# Microcontroller.net
KiCad netlist of a schematic drawn in Altium Designer
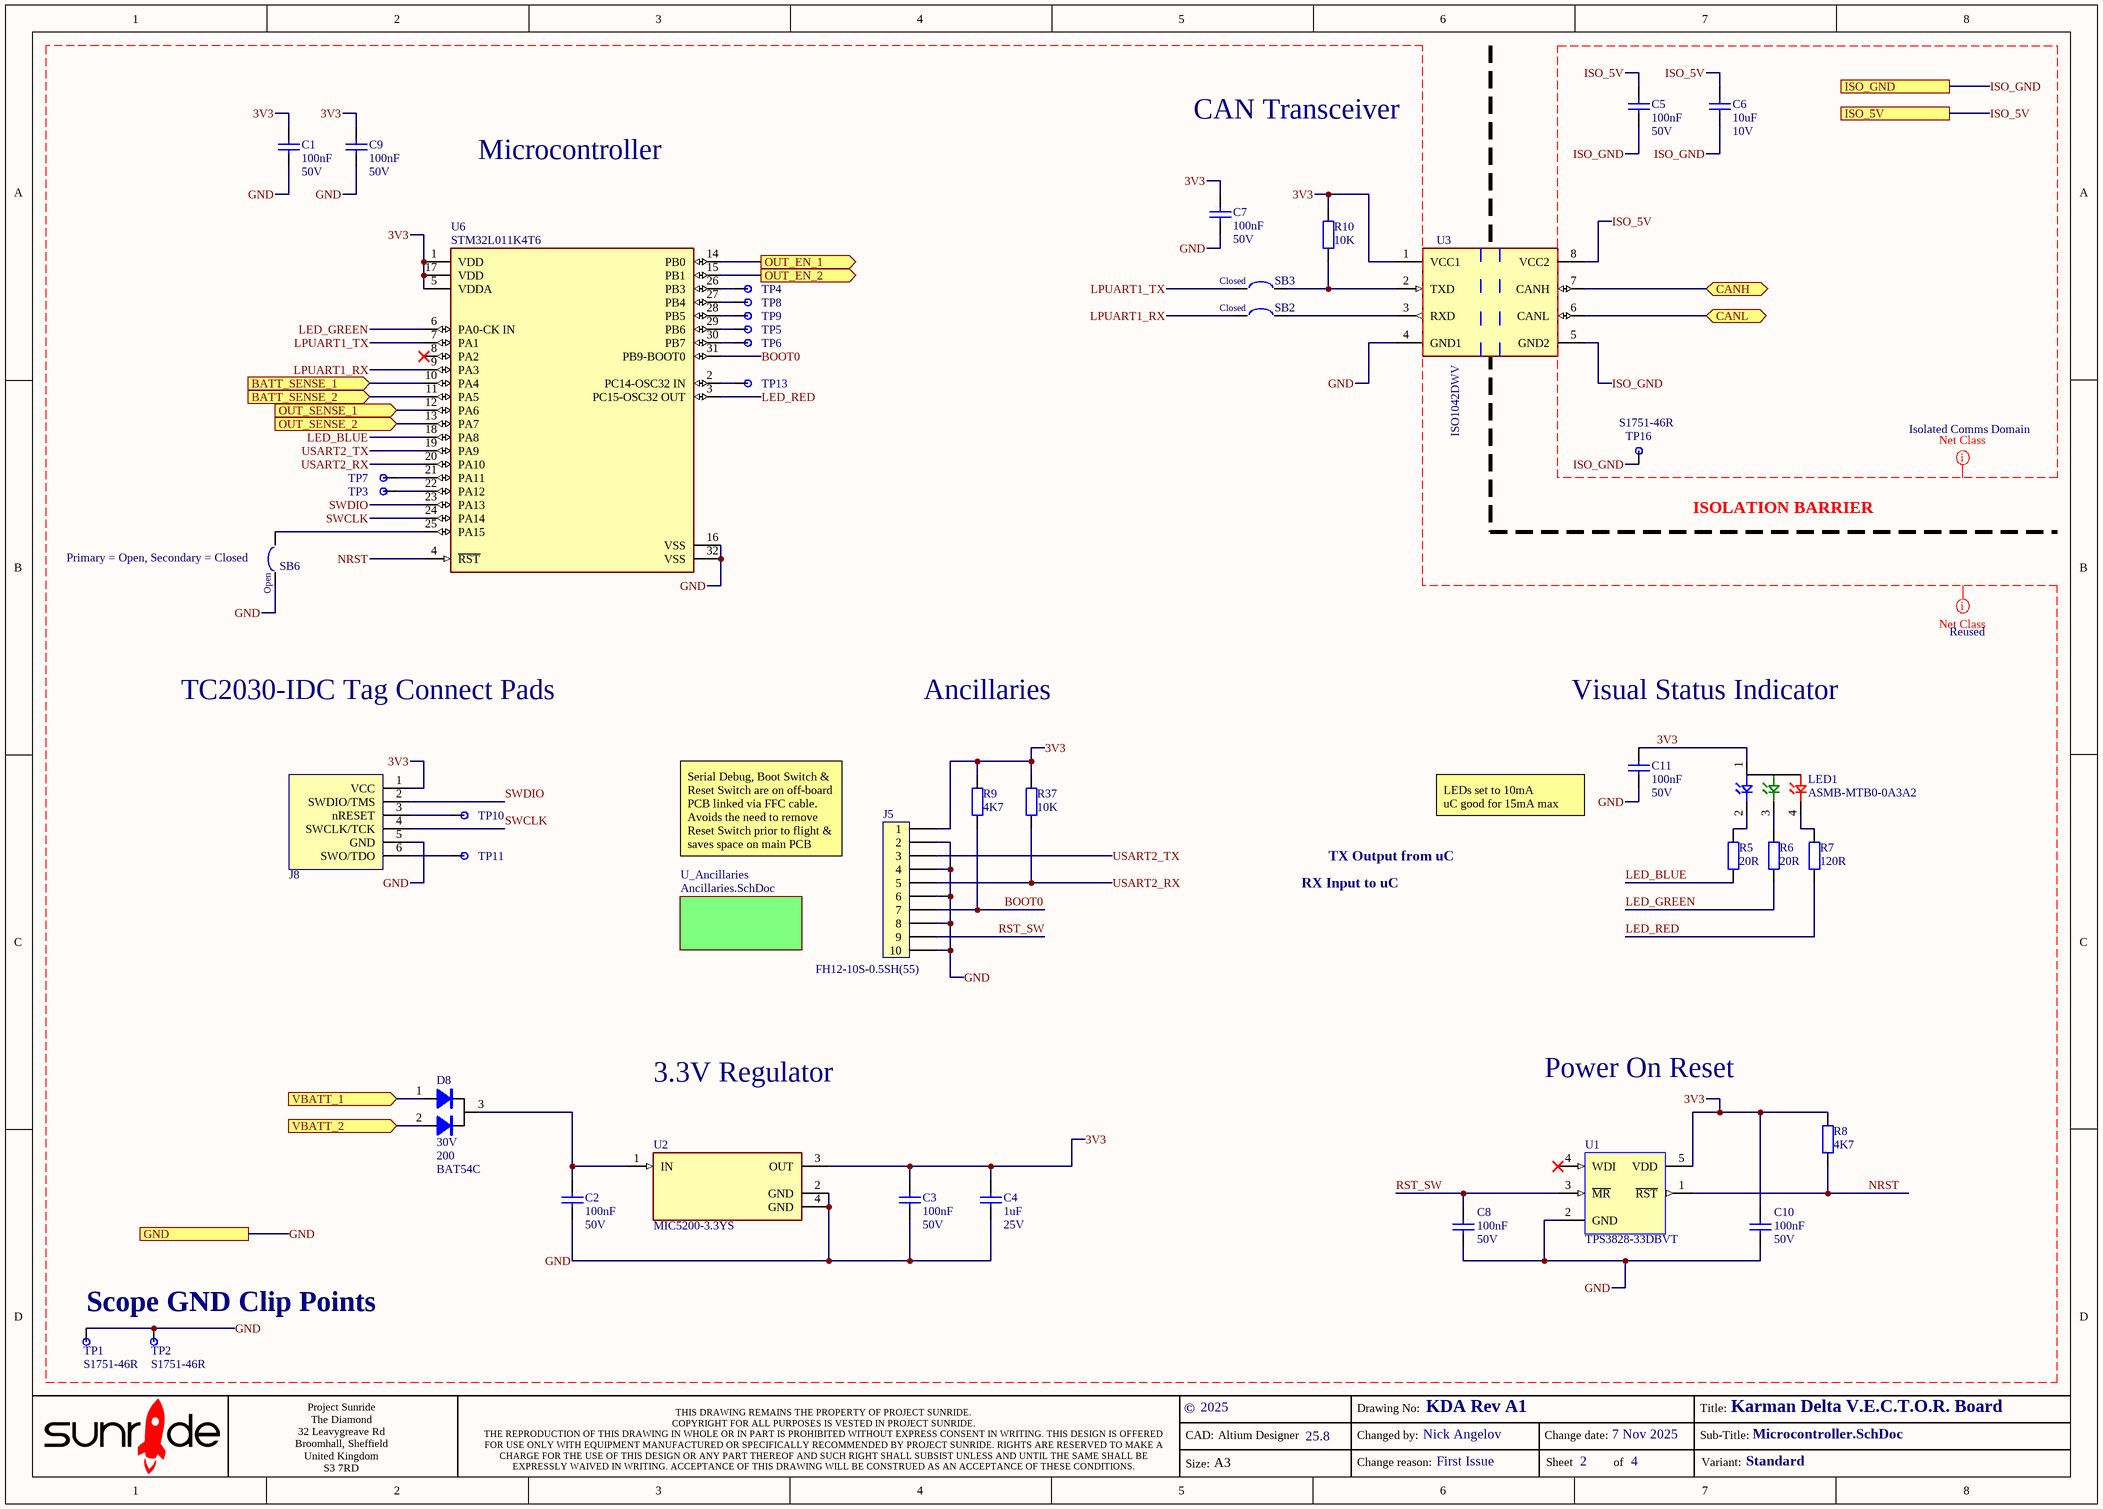
[diagram p0: Microcontroller.SchDoc]

(export (version "E")
  (design (tool "Eeschema 10.0.6"))
  (components
    (comp (ref "C1")
      (value "100nF")
      (footprint "CAPC1608X08L")
      (description "Capacitor MLC 100nF 50V X7R 10% CAPC1608X08M")
      (fields
        (field (name "VOLTAGE") "50V")
        (field (name "MANUFACTURER") "Murata")
        (field (name "MANUPARTNO") "GRM188R71H104KA93D")
      )
      (libsource (lib "Library") (part "CAP"))
    )
    (comp (ref "C2")
      (value "100nF")
      (footprint "CAPC1608X08L")
      (description "Capacitor MLC 100nF 50V X7R 10% CAPC1608X08M")
      (fields
        (field (name "VOLTAGE") "50V")
        (field (name "MANUFACTURER") "Murata")
        (field (name "MANUPARTNO") "GRM188R71H104KA93D")
      )
      (libsource (lib "Library") (part "CAP"))
    )
    (comp (ref "C3")
      (value "100nF")
      (footprint "CAPC1608X08L")
      (description "Capacitor MLC 100nF 50V X7R 10% CAPC1608X08M")
      (fields
        (field (name "VOLTAGE") "50V")
        (field (name "MANUFACTURER") "Murata")
        (field (name "MANUPARTNO") "GRM188R71H104KA93D")
      )
      (libsource (lib "Library") (part "CAP"))
    )
    (comp (ref "C4")
      (value "1uF")
      (footprint "CAPC1608X08L")
      (description "Capacitor MLC 1uF 25V X7R 10% CAPC1608X08M")
      (fields
        (field (name "VOLTAGE") "25V")
        (field (name "MANUFACTURER") "Samsung")
        (field (name "MANUPARTNO") "CL10B105KA8NFNC")
      )
      (libsource (lib "Library") (part "CAP"))
    )
    (comp (ref "C5")
      (value "100nF")
      (footprint "CAPC1608X08L")
      (description "Capacitor MLC 100nF 50V X7R 10% CAPC1608X08M")
      (fields
        (field (name "VOLTAGE") "50V")
        (field (name "MANUFACTURER") "Murata")
        (field (name "MANUPARTNO") "GRM188R71H104KA93D")
      )
      (libsource (lib "") (part "CAP_1"))
    )
    (comp (ref "C6")
      (value "10uF")
      (footprint "CAPC2012X15M")
      (description "Capacitor MLC 10uF10V X7R 10% CAPC2012X15M")
      (fields
        (field (name "VOLTAGE") "10V")
        (field (name "MANUFACTURER") "Murata")
        (field (name "MANUPARTNO") "GRM21BR71A106KE51L")
      )
      (libsource (lib "Library") (part "CAP"))
    )
    (comp (ref "C7")
      (value "100nF")
      (footprint "CAPC1608X08L")
      (description "Capacitor MLC 100nF 50V X7R 10% CAPC1608X08M")
      (fields
        (field (name "VOLTAGE") "50V")
        (field (name "MANUFACTURER") "Murata")
        (field (name "MANUPARTNO") "GRM188R71H104KA93D")
      )
      (libsource (lib "") (part "CAP_1"))
    )
    (comp (ref "C8")
      (value "100nF")
      (footprint "CAPC1608X08L")
      (description "Capacitor MLC 100nF 50V X7R 10% CAPC1608X08M")
      (fields
        (field (name "VOLTAGE") "50V")
        (field (name "MANUFACTURER") "Murata")
        (field (name "MANUPARTNO") "GRM188R71H104KA93D")
      )
      (libsource (lib "Library") (part "CAP"))
    )
    (comp (ref "C9")
      (value "100nF")
      (footprint "CAPC1608X08L")
      (description "Capacitor MLC 100nF 50V X7R 10% CAPC1608X08M")
      (fields
        (field (name "VOLTAGE") "50V")
        (field (name "MANUFACTURER") "Murata")
        (field (name "MANUPARTNO") "GRM188R71H104KA93D")
      )
      (libsource (lib "Library") (part "CAP"))
    )
    (comp (ref "C10")
      (value "100nF")
      (footprint "CAPC1608X08L")
      (description "Capacitor MLC 100nF 50V X7R 10% CAPC1608X08M")
      (fields
        (field (name "VOLTAGE") "50V")
        (field (name "MANUFACTURER") "Murata")
        (field (name "MANUPARTNO") "GRM188R71H104KA93D")
      )
      (libsource (lib "Library") (part "CAP"))
    )
    (comp (ref "C11")
      (value "100nF")
      (footprint "CAPC1608X08L")
      (description "Capacitor MLC 100nF 50V X7R 10% CAPC1608X08M")
      (fields
        (field (name "VOLTAGE") "50V")
        (field (name "MANUFACTURER") "Murata")
        (field (name "MANUPARTNO") "GRM188R71H104KA93D")
      )
      (libsource (lib "") (part "CAP_1"))
    )
    (comp (ref "D8")
      (value "*")
      (footprint "SOT95P237X112-3M")
      (description "Diode Schottky BAT54C SOT-23")
      (fields
        (field (name "VR (V)") "30V")
        (field (name "IF (MA)") "200")
        (field (name "MANUPARTNO") "BAT54C")
        (field (name "MANUFACTURER") "Fairchild")
      )
      (libsource (lib "Library") (part "DIODESOT23C"))
    )
    (comp (ref "J5")
      (value "Ancillaries")
      (footprint "FH12-10S-0_5SH")
      (description "Connector 10W FFC/FPC 0.5mm SM ZIF")
      (fields (field (name "MANUPARTNO") "FH12-10S-0.5SH(55)") (field (name "MANUFACTURER") "Hirose"))
      (libsource (lib "Library") (part "CON10"))
    )
    (comp (ref "J8")
      (value "TC2030-IDC Tag Connect Pads")
      (footprint "TC2030-IDC-NL")
      (description "TC2030 Tag Connect Programmer Connection - Non BOM part")
      (fields (field (name "MANUFACTURER") "Tag Connect"))
      (libsource (lib "Library") (part "TC2030-IDC"))
    )
    (comp (ref "LED1")
      (value "Visual Status Indicator")
      (footprint "ASMB-MTB0-0A3A2")
      (description "LED RGB, SMD, 2.4mm, 115 °")
      (fields (field (name "MANUPARTNO") "ASMB-MTB0-0A3A2") (field (name "MANUFACTURER") "Wurth"))
      (libsource (lib "Library") (part "LED_RGB"))
    )
    (comp (ref "R5")
      (value "20R")
      (footprint "RESC1608X06L")
      (description "Resistor 20R 1% 50V RESC1608X06M")
      (fields (field (name "VOLTAGE") "50V") (field (name "MANUFACTURER") "Multicomp"))
      (libsource (lib "Library") (part "RESISTOR"))
    )
    (comp (ref "R6")
      (value "20R")
      (footprint "RESC1608X06L")
      (description "Resistor 20R 1% 50V RESC1608X06M")
      (fields (field (name "VOLTAGE") "50V") (field (name "MANUFACTURER") "Multicomp"))
      (libsource (lib "Library") (part "RESISTOR"))
    )
    (comp (ref "R7")
      (value "120R")
      (footprint "RESC1608X06L")
      (description "Resistor 120R 1% 50V RESC1608X06M")
      (fields (field (name "VOLTAGE") "50V") (field (name "MANUFACTURER") "Multicomp"))
      (libsource (lib "Library") (part "RESISTOR"))
    )
    (comp (ref "R8")
      (value "4K7")
      (footprint "RESC1608X06L")
      (description "Resistor 4K7 1% 50V RESC1608X06M")
      (fields (field (name "VOLTAGE") "50V") (field (name "MANUFACTURER") "Multicomp"))
      (libsource (lib "Library") (part "RESISTOR"))
    )
    (comp (ref "R9")
      (value "4K7")
      (footprint "RESC1608X06L")
      (description "Resistor 4K7 1% 50V RESC1608X06M")
      (fields (field (name "VOLTAGE") "50V") (field (name "MANUFACTURER") "Multicomp"))
      (libsource (lib "Library") (part "RESISTOR"))
    )
    (comp (ref "R10")
      (value "10K")
      (footprint "RESC1608X06L")
      (description "SMD Chip Resistor, Thin Film, 10 kohm, 75 V, 0603 [1608 Metric], 100 mW, ± 0.1%, ERA3A Series")
      (fields (field (name "VOLTAGE") "75V") (field (name "MANUFACTURER") "Panasonic"))
      (libsource (lib "") (part "RESISTOR_1"))
    )
    (comp (ref "R37")
      (value "10K")
      (footprint "RESC1608X06L")
      (description "SMD Chip Resistor, Thin Film, 10 kohm, 75 V, 0603 [1608 Metric], 100 mW, ± 0.1%, ERA3A Series")
      (fields (field (name "VOLTAGE") "75V") (field (name "MANUFACTURER") "Panasonic"))
      (libsource (lib "") (part "RESISTOR_1"))
    )
    (comp (ref "SB2")
      (value "Solder Blob Closed")
      (footprint "0603SolderLinkClosed")
      (description "Solder Blob - Closed 0603 SM pads")
      (libsource (lib "Library") (part "Solder Blob Closed"))
    )
    (comp (ref "SB3")
      (value "Solder Blob Closed")
      (footprint "0603SolderLinkClosed")
      (description "Solder Blob - Closed 0603 SM pads")
      (libsource (lib "Library") (part "Solder Blob Closed"))
    )
    (comp (ref "SB6")
      (value "Primary = Open, Secondary = Closed")
      (footprint "0603SolderLinkOpen")
      (description "Solder Blob - Open 0603 SM pads")
      (libsource (lib "Library") (part "Solder Blob Open"))
    )
    (comp (ref "TP1")
      (value "GND")
      (footprint "S1751-46R")
      (description "PCB Test Point S1751 Series, Surface Mount")
      (fields (field (name "MANUPARTNO") "S1751-46R") (field (name "MANUFACTURER") "Harwin"))
      (libsource (lib "Library") (part "TP1-fitted"))
    )
    (comp (ref "TP2")
      (value "GND")
      (footprint "S1751-46R")
      (description "PCB Test Point S1751 Series, Surface Mount")
      (fields (field (name "MANUPARTNO") "S1751-46R") (field (name "MANUFACTURER") "Harwin"))
      (libsource (lib "Library") (part "TP1-fitted"))
    )
    (comp (ref "TP3")
      (value "TMS")
      (footprint "TP1")
      (description "Testpoint 1mm dia. Component side, no silk")
      (libsource (lib "Library") (part "TP1"))
    )
    (comp (ref "TP4")
      (value "TMS")
      (footprint "TP1")
      (description "Testpoint 1mm dia. Component side, no silk")
      (libsource (lib "Library") (part "TP1"))
    )
    (comp (ref "TP5")
      (value "TMS")
      (footprint "TP1")
      (description "Testpoint 1mm dia. Component side, no silk")
      (libsource (lib "Library") (part "TP1"))
    )
    (comp (ref "TP6")
      (value "TMS")
      (footprint "TP1")
      (description "Testpoint 1mm dia. Component side, no silk")
      (libsource (lib "Library") (part "TP1"))
    )
    (comp (ref "TP7")
      (value "TMS")
      (footprint "TP1")
      (description "Testpoint 1mm dia. Component side, no silk")
      (libsource (lib "Library") (part "TP1"))
    )
    (comp (ref "TP8")
      (value "TMS")
      (footprint "TP1")
      (description "Testpoint 1mm dia. Component side, no silk")
      (libsource (lib "Library") (part "TP1"))
    )
    (comp (ref "TP9")
      (value "TMS")
      (footprint "TP1")
      (description "Testpoint 1mm dia. Component side, no silk")
      (libsource (lib "Library") (part "TP1"))
    )
    (comp (ref "TP10")
      (value "TMS")
      (footprint "TP1")
      (description "Testpoint 1mm dia. Component side, no silk")
      (libsource (lib "Library") (part "TP1"))
    )
    (comp (ref "TP11")
      (value "TMS")
      (footprint "TP1")
      (description "Testpoint 1mm dia. Component side, no silk")
      (libsource (lib "Library") (part "TP1"))
    )
    (comp (ref "TP13")
      (value "TMS")
      (footprint "TP1")
      (description "Testpoint 1mm dia. Component side, no silk")
      (libsource (lib "Library") (part "TP1"))
    )
    (comp (ref "TP16")
      (value "GND")
      (footprint "S1751-46R")
      (description "PCB Test Point S1751 Series, Surface Mount")
      (fields (field (name "MANUPARTNO") "S1751-46R") (field (name "MANUFACTURER") "Harwin"))
      (libsource (lib "Library") (part "TP1-fitted"))
    )
    (comp (ref "U1")
      (value "Power On Reset")
      (footprint "SOT95P280X145-5L")
      (description "IC Supply Voltage Monitor, 2.93V TPS3828-33DBVT SOT23-5")
      (fields (field (name "MANUPARTNO") "TPS3828-33DBVT") (field (name "MANUFACTURER") "Texas"))
      (libsource (lib "Library") (part "VSENSE5"))
    )
    (comp (ref "U2")
      (value "MIC5200-3.3YS")
      (footprint "FP-SOT223-3LD-PL-1-IPC_C")
      (description "IC REG LIN 3.3V 100MA SOT223-3")
      (libsource (lib "Altium Content Vault") (part "f5128a9f8ed94365bfd39dcb8083813"))
    )
    (comp (ref "U3")
      (value "CAN Transceiver")
      (footprint "FP-DWV0008A-IPC_C")
      (description "IC TRANSCEIVER FULL 1/1 8SOIC")
      (fields (field (name "MANUF PART NO") "ISO1042DWV"))
      (libsource (lib "Altium Content Vault") (part "909e5d76d32ef4d3bd4dfdc3f0018f8"))
    )
    (comp (ref "U6")
      (value "Microcontroller")
      (footprint "FP-LQFP32-5V-MFG")
      (description "IC MCU 32BIT 16KB FLASH 32LQFP")
      (fields
        (field (name "MANUFACTURER PART NUMBER") "STM32L011K4T6")
        (field (name "MANUFACTURER") "STMicroelectronics")
        (field (name "OCTOPART") "https://octopart.com/stm32l011k4t6-stmicroelectronics-71108062")
      )
      (libsource (lib "Altium Content Vault") (part "3cbf9028c7ade503566d0a55c35e94d"))
    )
  )
  (nets
    (net (code "1") (name "/3V3") (class "Default")
      (node (ref "C1") (pin "1") (pinfunction "1_1") (pintype "passive"))
      (node (ref "C10") (pin "1") (pinfunction "1_1") (pintype "passive"))
      (node (ref "C11") (pin "1") (pinfunction "1_1") (pintype "passive"))
      (node (ref "C3") (pin "1") (pinfunction "1_1") (pintype "passive"))
      (node (ref "C4") (pin "1") (pinfunction "1_1") (pintype "passive"))
      (node (ref "C7") (pin "1") (pinfunction "1_1") (pintype "passive"))
      (node (ref "C9") (pin "1") (pinfunction "1_1") (pintype "passive"))
      (node (ref "J5") (pin "1") (pinfunction "1_1") (pintype "passive"))
      (node (ref "J8") (pin "1") (pinfunction "VCC_1") (pintype "passive"))
      (node (ref "LED1") (pin "1") (pinfunction "A_1") (pintype "passive"))
      (node (ref "R10") (pin "2") (pinfunction "2_2") (pintype "passive"))
      (node (ref "R37") (pin "2") (pinfunction "2_2") (pintype "passive"))
      (node (ref "R8") (pin "2") (pinfunction "2_2") (pintype "passive"))
      (node (ref "R9") (pin "2") (pinfunction "2_2") (pintype "passive"))
      (node (ref "U1") (pin "5") (pinfunction "VDD_5") (pintype "power_in"))
      (node (ref "U2") (pin "3") (pinfunction "OUT_3") (pintype "power_in"))
      (node (ref "U3") (pin "1") (pinfunction "VCC1_1") (pintype "power_in"))
      (node (ref "U6") (pin "1") (pinfunction "VDD_1") (pintype "power_in"))
      (node (ref "U6") (pin "17") (pinfunction "VDD_17") (pintype "power_in"))
      (node (ref "U6") (pin "5") (pinfunction "VDDA_5") (pintype "power_in"))
    )
    (net (code "2") (name "/BATT_SENSE_1") (class "Default")
      (node (ref "U6") (pin "10") (pinfunction "PA4_10") (pintype "bidirectional"))
    )
    (net (code "3") (name "/BATT_SENSE_2") (class "Default")
      (node (ref "U6") (pin "11") (pinfunction "PA5_11") (pintype "bidirectional"))
    )
    (net (code "4") (name "/BOOT0") (class "Default")
      (node (ref "J5") (pin "7") (pinfunction "7_7") (pintype "passive"))
      (node (ref "R9") (pin "1") (pinfunction "1_1") (pintype "passive"))
      (node (ref "U6") (pin "31") (pinfunction "PB9-BOOT0_31") (pintype "bidirectional"))
    )
    (net (code "5") (name "/CANH") (class "Default")
      (node (ref "U3") (pin "7") (pinfunction "CANH_7") (pintype "bidirectional"))
    )
    (net (code "6") (name "/CANL") (class "Default")
      (node (ref "U3") (pin "6") (pinfunction "CANL_6") (pintype "bidirectional"))
    )
    (net (code "7") (name "/GND") (class "Default")
      (node (ref "C1") (pin "2") (pinfunction "2_2") (pintype "passive"))
      (node (ref "C10") (pin "2") (pinfunction "2_2") (pintype "passive"))
      (node (ref "C11") (pin "2") (pinfunction "2_2") (pintype "passive"))
      (node (ref "C2") (pin "2") (pinfunction "2_2") (pintype "passive"))
      (node (ref "C3") (pin "2") (pinfunction "2_2") (pintype "passive"))
      (node (ref "C4") (pin "2") (pinfunction "2_2") (pintype "passive"))
      (node (ref "C7") (pin "2") (pinfunction "2_2") (pintype "passive"))
      (node (ref "C8") (pin "2") (pinfunction "2_2") (pintype "passive"))
      (node (ref "C9") (pin "2") (pinfunction "2_2") (pintype "passive"))
      (node (ref "J5") (pin "10") (pinfunction "10_10") (pintype "passive"))
      (node (ref "J5") (pin "2") (pinfunction "2_2") (pintype "passive"))
      (node (ref "J5") (pin "4") (pinfunction "4_4") (pintype "passive"))
      (node (ref "J5") (pin "6") (pinfunction "6_6") (pintype "passive"))
      (node (ref "J5") (pin "8") (pinfunction "8_8") (pintype "passive"))
      (node (ref "J8") (pin "5") (pinfunction "GND_5") (pintype "passive"))
      (node (ref "SB6") (pin "1") (pinfunction "1_1") (pintype "passive"))
      (node (ref "TP1") (pin "1") (pintype "passive"))
      (node (ref "TP2") (pin "1") (pintype "passive"))
      (node (ref "U1") (pin "2") (pinfunction "GND_2") (pintype "passive"))
      (node (ref "U2") (pin "2") (pinfunction "GND_2") (pintype "power_in"))
      (node (ref "U2") (pin "4") (pinfunction "GND_4") (pintype "power_in"))
      (node (ref "U3") (pin "4") (pinfunction "GND1_4") (pintype "power_in"))
      (node (ref "U6") (pin "16") (pinfunction "VSS_16") (pintype "power_in"))
      (node (ref "U6") (pin "32") (pinfunction "VSS_32") (pintype "power_in"))
    )
    (net (code "8") (name "/ISO_5V") (class "Default")
      (node (ref "C5") (pin "1") (pinfunction "1_1") (pintype "passive"))
      (node (ref "C6") (pin "1") (pinfunction "1_1") (pintype "passive"))
      (node (ref "U3") (pin "8") (pinfunction "VCC2_8") (pintype "power_in"))
    )
    (net (code "9") (name "/ISO_GND") (class "Default")
      (node (ref "C5") (pin "2") (pinfunction "2_2") (pintype "passive"))
      (node (ref "C6") (pin "2") (pinfunction "2_2") (pintype "passive"))
      (node (ref "TP16") (pin "1") (pintype "passive"))
      (node (ref "U3") (pin "5") (pinfunction "GND2_5") (pintype "power_in"))
    )
    (net (code "10") (name "/LED_BLUE") (class "Default")
      (node (ref "R5") (pin "1") (pinfunction "1_1") (pintype "passive"))
      (node (ref "U6") (pin "18") (pinfunction "PA8_18") (pintype "bidirectional"))
    )
    (net (code "11") (name "/LED_GREEN") (class "Default")
      (node (ref "R6") (pin "1") (pinfunction "1_1") (pintype "passive"))
      (node (ref "U6") (pin "6") (pinfunction "PA0-CK_IN_6") (pintype "bidirectional"))
    )
    (net (code "12") (name "/LED_RED") (class "Default")
      (node (ref "R7") (pin "1") (pinfunction "1_1") (pintype "passive"))
      (node (ref "U6") (pin "3") (pinfunction "PC15-OSC32_OUT_3") (pintype "bidirectional"))
    )
    (net (code "13") (name "/LPUART1_RX") (class "Default")
      (node (ref "SB2") (pin "1") (pinfunction "1_1") (pintype "passive"))
      (node (ref "U6") (pin "9") (pinfunction "PA3_9") (pintype "bidirectional"))
    )
    (net (code "14") (name "/LPUART1_TX") (class "Default")
      (node (ref "SB3") (pin "1") (pinfunction "1_1") (pintype "passive"))
      (node (ref "U6") (pin "7") (pinfunction "PA1_7") (pintype "bidirectional"))
    )
    (net (code "15") (name "/NRST") (class "Default")
      (node (ref "R8") (pin "1") (pinfunction "1_1") (pintype "passive"))
      (node (ref "U1") (pin "1") (pinfunction "RST_1") (pintype "output"))
      (node (ref "U6") (pin "4") (pinfunction "~{RST}_4") (pintype "input"))
    )
    (net (code "16") (name "/OUT_EN_1") (class "Default")
      (node (ref "U6") (pin "14") (pinfunction "PB0_14") (pintype "bidirectional"))
    )
    (net (code "17") (name "/OUT_EN_2") (class "Default")
      (node (ref "U6") (pin "15") (pinfunction "PB1_15") (pintype "bidirectional"))
    )
    (net (code "18") (name "/OUT_SENSE_1") (class "Default")
      (node (ref "U6") (pin "12") (pinfunction "PA6_12") (pintype "bidirectional"))
    )
    (net (code "19") (name "/OUT_SENSE_2") (class "Default")
      (node (ref "U6") (pin "13") (pinfunction "PA7_13") (pintype "bidirectional"))
    )
    (net (code "20") (name "/RST_SW") (class "Default")
      (node (ref "C8") (pin "1") (pinfunction "1_1") (pintype "passive"))
      (node (ref "J5") (pin "9") (pinfunction "9_9") (pintype "passive"))
      (node (ref "U1") (pin "3") (pinfunction "MR_3") (pintype "input"))
    )
    (net (code "21") (name "/SWCLK") (class "Default")
      (node (ref "J8") (pin "4") (pinfunction "SWCLK/TCK_4") (pintype "passive"))
      (node (ref "U6") (pin "24") (pinfunction "PA14_24") (pintype "bidirectional"))
    )
    (net (code "22") (name "/SWDIO") (class "Default")
      (node (ref "J8") (pin "2") (pinfunction "SWDIO/TMS_2") (pintype "passive"))
      (node (ref "U6") (pin "23") (pinfunction "PA13_23") (pintype "bidirectional"))
    )
    (net (code "23") (name "/USART2_RX") (class "Default")
      (node (ref "J5") (pin "5") (pinfunction "5_5") (pintype "passive"))
      (node (ref "R37") (pin "1") (pinfunction "1_1") (pintype "passive"))
      (node (ref "U6") (pin "20") (pinfunction "PA10_20") (pintype "bidirectional"))
    )
    (net (code "24") (name "/USART2_TX") (class "Default")
      (node (ref "J5") (pin "3") (pinfunction "3_3") (pintype "passive"))
      (node (ref "U6") (pin "19") (pinfunction "PA9_19") (pintype "bidirectional"))
    )
    (net (code "25") (name "/VBATT_1") (class "Default")
      (node (ref "D8") (pin "1") (pinfunction "1_1") (pintype "passive"))
    )
    (net (code "26") (name "/VBATT_2") (class "Default")
      (node (ref "D8") (pin "2") (pinfunction "2_2") (pintype "passive"))
    )
    (net (code "27") (name "Net-(J8-SWO{slash}TDO)") (class "Default")
      (node (ref "J8") (pin "6") (pinfunction "SWO/TDO_6") (pintype "passive"))
      (node (ref "TP11") (pin "1") (pintype "passive"))
    )
    (net (code "28") (name "Net-(J8-nRESET)") (class "Default")
      (node (ref "J8") (pin "3") (pinfunction "nRESET_3") (pintype "passive"))
      (node (ref "TP10") (pin "1") (pintype "passive"))
    )
    (net (code "29") (name "Net-(LED1-B)") (class "Default")
      (node (ref "LED1") (pin "2") (pinfunction "B_2") (pintype "passive"))
      (node (ref "R5") (pin "2") (pinfunction "2_2") (pintype "passive"))
    )
    (net (code "30") (name "Net-(LED1-G)") (class "Default")
      (node (ref "LED1") (pin "3") (pinfunction "G_3") (pintype "passive"))
      (node (ref "R6") (pin "2") (pinfunction "2_2") (pintype "passive"))
    )
    (net (code "31") (name "Net-(LED1-R)") (class "Default")
      (node (ref "LED1") (pin "4") (pinfunction "R_4") (pintype "passive"))
      (node (ref "R7") (pin "2") (pinfunction "2_2") (pintype "passive"))
    )
    (net (code "32") (name "Net-(U2-IN)") (class "Default")
      (node (ref "C2") (pin "1") (pinfunction "1_1") (pintype "passive"))
      (node (ref "D8") (pin "3") (pinfunction "3_3") (pintype "passive"))
      (node (ref "U2") (pin "1") (pinfunction "IN_1") (pintype "input"))
    )
    (net (code "33") (name "Net-(U3-RXD)") (class "Default")
      (node (ref "SB2") (pin "2") (pinfunction "2_2") (pintype "passive"))
      (node (ref "U3") (pin "3") (pinfunction "RXD_3") (pintype "output"))
    )
    (net (code "34") (name "Net-(U3-TXD)") (class "Default")
      (node (ref "R10") (pin "1") (pinfunction "1_1") (pintype "passive"))
      (node (ref "SB3") (pin "2") (pinfunction "2_2") (pintype "passive"))
      (node (ref "U3") (pin "2") (pinfunction "TXD_2") (pintype "input"))
    )
    (net (code "35") (name "Net-(U6-PA11)") (class "Default")
      (node (ref "TP7") (pin "1") (pintype "passive"))
      (node (ref "U6") (pin "21") (pinfunction "PA11_21") (pintype "bidirectional"))
    )
    (net (code "36") (name "Net-(U6-PA12)") (class "Default")
      (node (ref "TP3") (pin "1") (pintype "passive"))
      (node (ref "U6") (pin "22") (pinfunction "PA12_22") (pintype "bidirectional"))
    )
    (net (code "37") (name "Net-(U6-PA15)") (class "Default")
      (node (ref "SB6") (pin "2") (pinfunction "2_2") (pintype "passive"))
      (node (ref "U6") (pin "25") (pinfunction "PA15_25") (pintype "bidirectional"))
    )
    (net (code "38") (name "Net-(U6-PB3)") (class "Default")
      (node (ref "TP4") (pin "1") (pintype "passive"))
      (node (ref "U6") (pin "26") (pinfunction "PB3_26") (pintype "bidirectional"))
    )
    (net (code "39") (name "Net-(U6-PB4)") (class "Default")
      (node (ref "TP8") (pin "1") (pintype "passive"))
      (node (ref "U6") (pin "27") (pinfunction "PB4_27") (pintype "bidirectional"))
    )
    (net (code "40") (name "Net-(U6-PB5)") (class "Default")
      (node (ref "TP9") (pin "1") (pintype "passive"))
      (node (ref "U6") (pin "28") (pinfunction "PB5_28") (pintype "bidirectional"))
    )
    (net (code "41") (name "Net-(U6-PB6)") (class "Default")
      (node (ref "TP5") (pin "1") (pintype "passive"))
      (node (ref "U6") (pin "29") (pinfunction "PB6_29") (pintype "bidirectional"))
    )
    (net (code "42") (name "Net-(U6-PB7)") (class "Default")
      (node (ref "TP6") (pin "1") (pintype "passive"))
      (node (ref "U6") (pin "30") (pinfunction "PB7_30") (pintype "bidirectional"))
    )
    (net (code "43") (name "Net-(U6-PC14-OSC32_IN)") (class "Default")
      (node (ref "TP13") (pin "1") (pintype "passive"))
      (node (ref "U6") (pin "2") (pinfunction "PC14-OSC32_IN_2") (pintype "bidirectional"))
    )
    (net (code "44") (name "unconnected-(U1-WDI-Pad4)") (class "Default")
      (node (ref "U1") (pin "4") (pinfunction "WDI_4") (pintype "input+no_connect"))
    )
    (net (code "45") (name "unconnected-(U6-PA2-Pad8)") (class "Default")
      (node (ref "U6") (pin "8") (pinfunction "PA2_8") (pintype "bidirectional+no_connect"))
    )
  )
)
